# Zuno.net
KiCad netlist of a schematic drawn in EAGLE
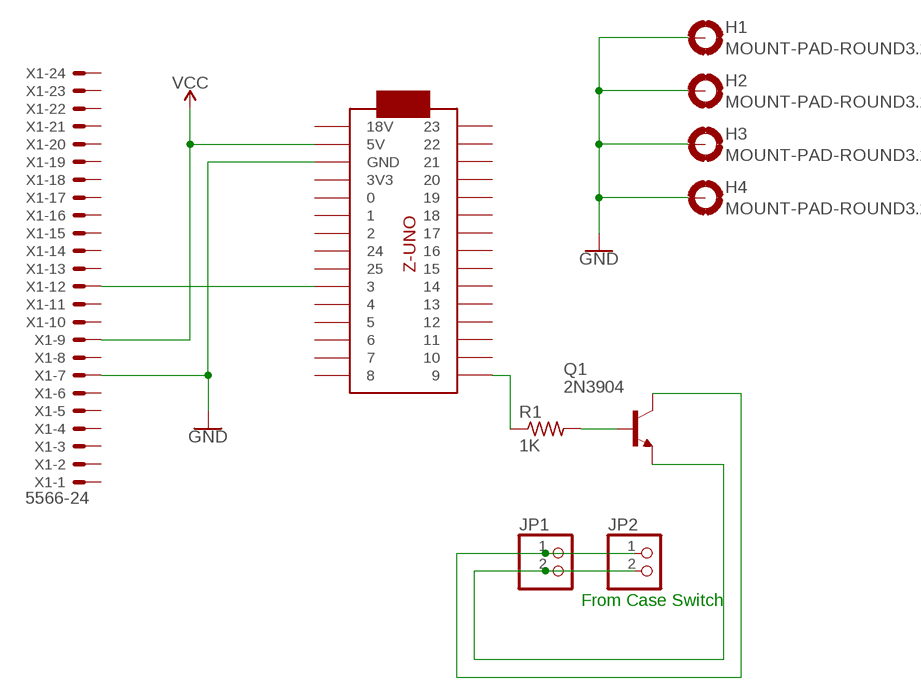
[diagram p0: schematic, sheet 1]

(export (version "E")
  (design (tool "Eeschema 10.0.6"))
  (components
    (comp (ref "H1")
      (value "MOUNT-PAD-ROUND3.2")
      (footprint "eagle-import:3,2-PAD")
      (libsource (lib "eagle-import") (part "MOUNT-PAD-ROUND3.2"))
    )
    (comp (ref "H2")
      (value "MOUNT-PAD-ROUND3.2")
      (footprint "eagle-import:3,2-PAD")
      (libsource (lib "eagle-import") (part "MOUNT-PAD-ROUND3.2"))
    )
    (comp (ref "H3")
      (value "MOUNT-PAD-ROUND3.2")
      (footprint "eagle-import:3,2-PAD")
      (libsource (lib "eagle-import") (part "MOUNT-PAD-ROUND3.2"))
    )
    (comp (ref "H4")
      (value "MOUNT-PAD-ROUND3.2")
      (footprint "eagle-import:3,2-PAD")
      (libsource (lib "eagle-import") (part "MOUNT-PAD-ROUND3.2"))
    )
    (comp (ref "JP1")
      (value "PINHD-1X2")
      (footprint "eagle-import:1X02")
      (libsource (lib "eagle-import") (part "PINHD-1X2"))
    )
    (comp (ref "JP2")
      (value "PINHD-1X2")
      (footprint "eagle-import:1X02")
      (libsource (lib "eagle-import") (part "PINHD-1X2"))
    )
    (comp (ref "Q1")
      (value "2N3904")
      (footprint "eagle-import:TO92")
      (libsource (lib "eagle-import") (part "2N3904"))
    )
    (comp (ref "R1")
      (value "1K")
      (footprint "eagle-import:0207_10")
      (libsource (lib "eagle-import") (part "R-US_0207/10"))
    )
    (comp (ref "U$1")
      (value "ZUNO")
      (footprint "eagle-import:ZUNO")
      (libsource (lib "eagle-import") (part "ZUNO"))
    )
    (comp (ref "X1")
      (value "5566-24")
      (footprint "eagle-import:5566-24")
      (libsource (lib "eagle-import") (part "5566-24"))
    )
  )
  (nets
    (net (code "1") (name "GND") (class "Default")
      (node (ref "H1") (pin "B3,2") (pinfunction "MOUNT_B3,2") (pintype "passive"))
      (node (ref "H2") (pin "B3,2") (pinfunction "MOUNT_B3,2") (pintype "passive"))
      (node (ref "H3") (pin "B3,2") (pinfunction "MOUNT_B3,2") (pintype "passive"))
      (node (ref "H4") (pin "B3,2") (pinfunction "MOUNT_B3,2") (pintype "passive"))
      (node (ref "U$1") (pin "P$3") (pinfunction "GND_P$3") (pintype "bidirectional"))
      (node (ref "X1") (pin "7") (pinfunction "S_7") (pintype "passive"))
    )
    (net (code "2") (name "Net-(Q1-B)") (class "Default")
      (node (ref "Q1") (pin "2") (pinfunction "B_2") (pintype "passive"))
      (node (ref "R1") (pin "2") (pinfunction "2_2") (pintype "passive"))
    )
    (net (code "3") (name "Net-(Q1-C)") (class "Default")
      (node (ref "JP1") (pin "1") (pinfunction "1_1") (pintype "passive"))
      (node (ref "JP2") (pin "1") (pinfunction "1_1") (pintype "passive"))
      (node (ref "Q1") (pin "1") (pinfunction "C_1") (pintype "passive"))
    )
    (net (code "4") (name "Net-(Q1-E)") (class "Default")
      (node (ref "JP1") (pin "2") (pinfunction "2_2") (pintype "passive"))
      (node (ref "JP2") (pin "2") (pinfunction "2_2") (pintype "passive"))
      (node (ref "Q1") (pin "3") (pinfunction "E_3") (pintype "passive"))
    )
    (net (code "5") (name "Net-(U$1-3)") (class "Default")
      (node (ref "U$1") (pin "P$10") (pinfunction "3_P$10") (pintype "bidirectional"))
      (node (ref "X1") (pin "12") (pinfunction "S_12") (pintype "passive"))
    )
    (net (code "6") (name "Net-(U$1-9)") (class "Default")
      (node (ref "R1") (pin "1") (pinfunction "1_1") (pintype "passive"))
      (node (ref "U$1") (pin "P$16") (pinfunction "9_P$16") (pintype "bidirectional"))
    )
    (net (code "7") (name "VCC") (class "Default")
      (node (ref "U$1") (pin "P$2") (pinfunction "5V_P$2") (pintype "bidirectional"))
      (node (ref "X1") (pin "9") (pinfunction "S_9") (pintype "passive"))
    )
    (net (code "8") (name "unconnected-(U$1-0-PadP$5)") (class "Default")
      (node (ref "U$1") (pin "P$5") (pinfunction "0_P$5") (pintype "bidirectional"))
    )
    (net (code "9") (name "unconnected-(U$1-1-PadP$6)") (class "Default")
      (node (ref "U$1") (pin "P$6") (pinfunction "1_P$6") (pintype "bidirectional"))
    )
    (net (code "10") (name "unconnected-(U$1-2-PadP$7)") (class "Default")
      (node (ref "U$1") (pin "P$7") (pinfunction "2_P$7") (pintype "bidirectional"))
    )
    (net (code "11") (name "unconnected-(U$1-3V3-PadP$4)") (class "Default")
      (node (ref "U$1") (pin "P$4") (pinfunction "3V3_P$4") (pintype "bidirectional"))
    )
    (net (code "12") (name "unconnected-(U$1-4-PadP$11)") (class "Default")
      (node (ref "U$1") (pin "P$11") (pinfunction "4_P$11") (pintype "bidirectional"))
    )
    (net (code "13") (name "unconnected-(U$1-5-PadP$12)") (class "Default")
      (node (ref "U$1") (pin "P$12") (pinfunction "5_P$12") (pintype "bidirectional"))
    )
    (net (code "14") (name "unconnected-(U$1-6-PadP$13)") (class "Default")
      (node (ref "U$1") (pin "P$13") (pinfunction "6_P$13") (pintype "bidirectional"))
    )
    (net (code "15") (name "unconnected-(U$1-7-PadP$14)") (class "Default")
      (node (ref "U$1") (pin "P$14") (pinfunction "7_P$14") (pintype "bidirectional"))
    )
    (net (code "16") (name "unconnected-(U$1-8-PadP$15)") (class "Default")
      (node (ref "U$1") (pin "P$15") (pinfunction "8_P$15") (pintype "bidirectional"))
    )
    (net (code "17") (name "unconnected-(U$1-10-PadP$17)") (class "Default")
      (node (ref "U$1") (pin "P$17") (pinfunction "10_P$17") (pintype "bidirectional"))
    )
    (net (code "18") (name "unconnected-(U$1-11-PadP$18)") (class "Default")
      (node (ref "U$1") (pin "P$18") (pinfunction "11_P$18") (pintype "bidirectional"))
    )
    (net (code "19") (name "unconnected-(U$1-12-PadP$19)") (class "Default")
      (node (ref "U$1") (pin "P$19") (pinfunction "12_P$19") (pintype "bidirectional"))
    )
    (net (code "20") (name "unconnected-(U$1-13-PadP$20)") (class "Default")
      (node (ref "U$1") (pin "P$20") (pinfunction "13_P$20") (pintype "bidirectional"))
    )
    (net (code "21") (name "unconnected-(U$1-14-PadP$21)") (class "Default")
      (node (ref "U$1") (pin "P$21") (pinfunction "14_P$21") (pintype "bidirectional"))
    )
    (net (code "22") (name "unconnected-(U$1-15-PadP$22)") (class "Default")
      (node (ref "U$1") (pin "P$22") (pinfunction "15_P$22") (pintype "bidirectional"))
    )
    (net (code "23") (name "unconnected-(U$1-16-PadP$23)") (class "Default")
      (node (ref "U$1") (pin "P$23") (pinfunction "16_P$23") (pintype "bidirectional"))
    )
    (net (code "24") (name "unconnected-(U$1-17-PadP$24)") (class "Default")
      (node (ref "U$1") (pin "P$24") (pinfunction "17_P$24") (pintype "bidirectional"))
    )
    (net (code "25") (name "unconnected-(U$1-18-PadP$25)") (class "Default")
      (node (ref "U$1") (pin "P$25") (pinfunction "18_P$25") (pintype "bidirectional"))
    )
    (net (code "26") (name "unconnected-(U$1-18V-PadP$1)") (class "Default")
      (node (ref "U$1") (pin "P$1") (pinfunction "18V_P$1") (pintype "bidirectional"))
    )
    (net (code "27") (name "unconnected-(U$1-19-PadP$26)") (class "Default")
      (node (ref "U$1") (pin "P$26") (pinfunction "19_P$26") (pintype "bidirectional"))
    )
    (net (code "28") (name "unconnected-(U$1-20-PadP$27)") (class "Default")
      (node (ref "U$1") (pin "P$27") (pinfunction "20_P$27") (pintype "bidirectional"))
    )
    (net (code "29") (name "unconnected-(U$1-21-PadP$28)") (class "Default")
      (node (ref "U$1") (pin "P$28") (pinfunction "21_P$28") (pintype "bidirectional"))
    )
    (net (code "30") (name "unconnected-(U$1-22-PadP$29)") (class "Default")
      (node (ref "U$1") (pin "P$29") (pinfunction "22_P$29") (pintype "bidirectional"))
    )
    (net (code "31") (name "unconnected-(U$1-23-PadP$30)") (class "Default")
      (node (ref "U$1") (pin "P$30") (pinfunction "23_P$30") (pintype "bidirectional"))
    )
    (net (code "32") (name "unconnected-(U$1-24-PadP$8)") (class "Default")
      (node (ref "U$1") (pin "P$8") (pinfunction "24_P$8") (pintype "bidirectional"))
    )
    (net (code "33") (name "unconnected-(U$1-25-PadP$9)") (class "Default")
      (node (ref "U$1") (pin "P$9") (pinfunction "25_P$9") (pintype "bidirectional"))
    )
    (net (code "34") (name "unconnected-(X1A-S-Pad1)") (class "Default")
      (node (ref "X1") (pin "1") (pinfunction "S_1") (pintype "passive"))
    )
    (net (code "35") (name "unconnected-(X1B-S-Pad10)") (class "Default")
      (node (ref "X1") (pin "10") (pinfunction "S_10") (pintype "passive"))
    )
    (net (code "36") (name "unconnected-(X1C-S-Pad11)") (class "Default")
      (node (ref "X1") (pin "11") (pinfunction "S_11") (pintype "passive"))
    )
    (net (code "37") (name "unconnected-(X1E-S-Pad13)") (class "Default")
      (node (ref "X1") (pin "13") (pinfunction "S_13") (pintype "passive"))
    )
    (net (code "38") (name "unconnected-(X1F-S-Pad14)") (class "Default")
      (node (ref "X1") (pin "14") (pinfunction "S_14") (pintype "passive"))
    )
    (net (code "39") (name "unconnected-(X1G-S-Pad15)") (class "Default")
      (node (ref "X1") (pin "15") (pinfunction "S_15") (pintype "passive"))
    )
    (net (code "40") (name "unconnected-(X1H-S-Pad16)") (class "Default")
      (node (ref "X1") (pin "16") (pinfunction "S_16") (pintype "passive"))
    )
    (net (code "41") (name "unconnected-(X1I-S-Pad17)") (class "Default")
      (node (ref "X1") (pin "17") (pinfunction "S_17") (pintype "passive"))
    )
    (net (code "42") (name "unconnected-(X1J-S-Pad18)") (class "Default")
      (node (ref "X1") (pin "18") (pinfunction "S_18") (pintype "passive"))
    )
    (net (code "43") (name "unconnected-(X1K-S-Pad19)") (class "Default")
      (node (ref "X1") (pin "19") (pinfunction "S_19") (pintype "passive"))
    )
    (net (code "44") (name "unconnected-(X1L-S-Pad2)") (class "Default")
      (node (ref "X1") (pin "2") (pinfunction "S_2") (pintype "passive"))
    )
    (net (code "45") (name "unconnected-(X1M-S-Pad20)") (class "Default")
      (node (ref "X1") (pin "20") (pinfunction "S_20") (pintype "passive"))
    )
    (net (code "46") (name "unconnected-(X1N-S-Pad21)") (class "Default")
      (node (ref "X1") (pin "21") (pinfunction "S_21") (pintype "passive"))
    )
    (net (code "47") (name "unconnected-(X1O-S-Pad22)") (class "Default")
      (node (ref "X1") (pin "22") (pinfunction "S_22") (pintype "passive"))
    )
    (net (code "48") (name "unconnected-(X1P-S-Pad23)") (class "Default")
      (node (ref "X1") (pin "23") (pinfunction "S_23") (pintype "passive"))
    )
    (net (code "49") (name "unconnected-(X1Q-S-Pad24)") (class "Default")
      (node (ref "X1") (pin "24") (pinfunction "S_24") (pintype "passive"))
    )
    (net (code "50") (name "unconnected-(X1R-S-Pad3)") (class "Default")
      (node (ref "X1") (pin "3") (pinfunction "S_3") (pintype "passive"))
    )
    (net (code "51") (name "unconnected-(X1S-S-Pad4)") (class "Default")
      (node (ref "X1") (pin "4") (pinfunction "S_4") (pintype "passive"))
    )
    (net (code "52") (name "unconnected-(X1T-S-Pad5)") (class "Default")
      (node (ref "X1") (pin "5") (pinfunction "S_5") (pintype "passive"))
    )
    (net (code "53") (name "unconnected-(X1U-S-Pad6)") (class "Default")
      (node (ref "X1") (pin "6") (pinfunction "S_6") (pintype "passive"))
    )
    (net (code "54") (name "unconnected-(X1W-S-Pad8)") (class "Default")
      (node (ref "X1") (pin "8") (pinfunction "S_8") (pintype "passive"))
    )
  )
)
